# LowLevelv3.net
KiCad netlist of a schematic drawn in EAGLE
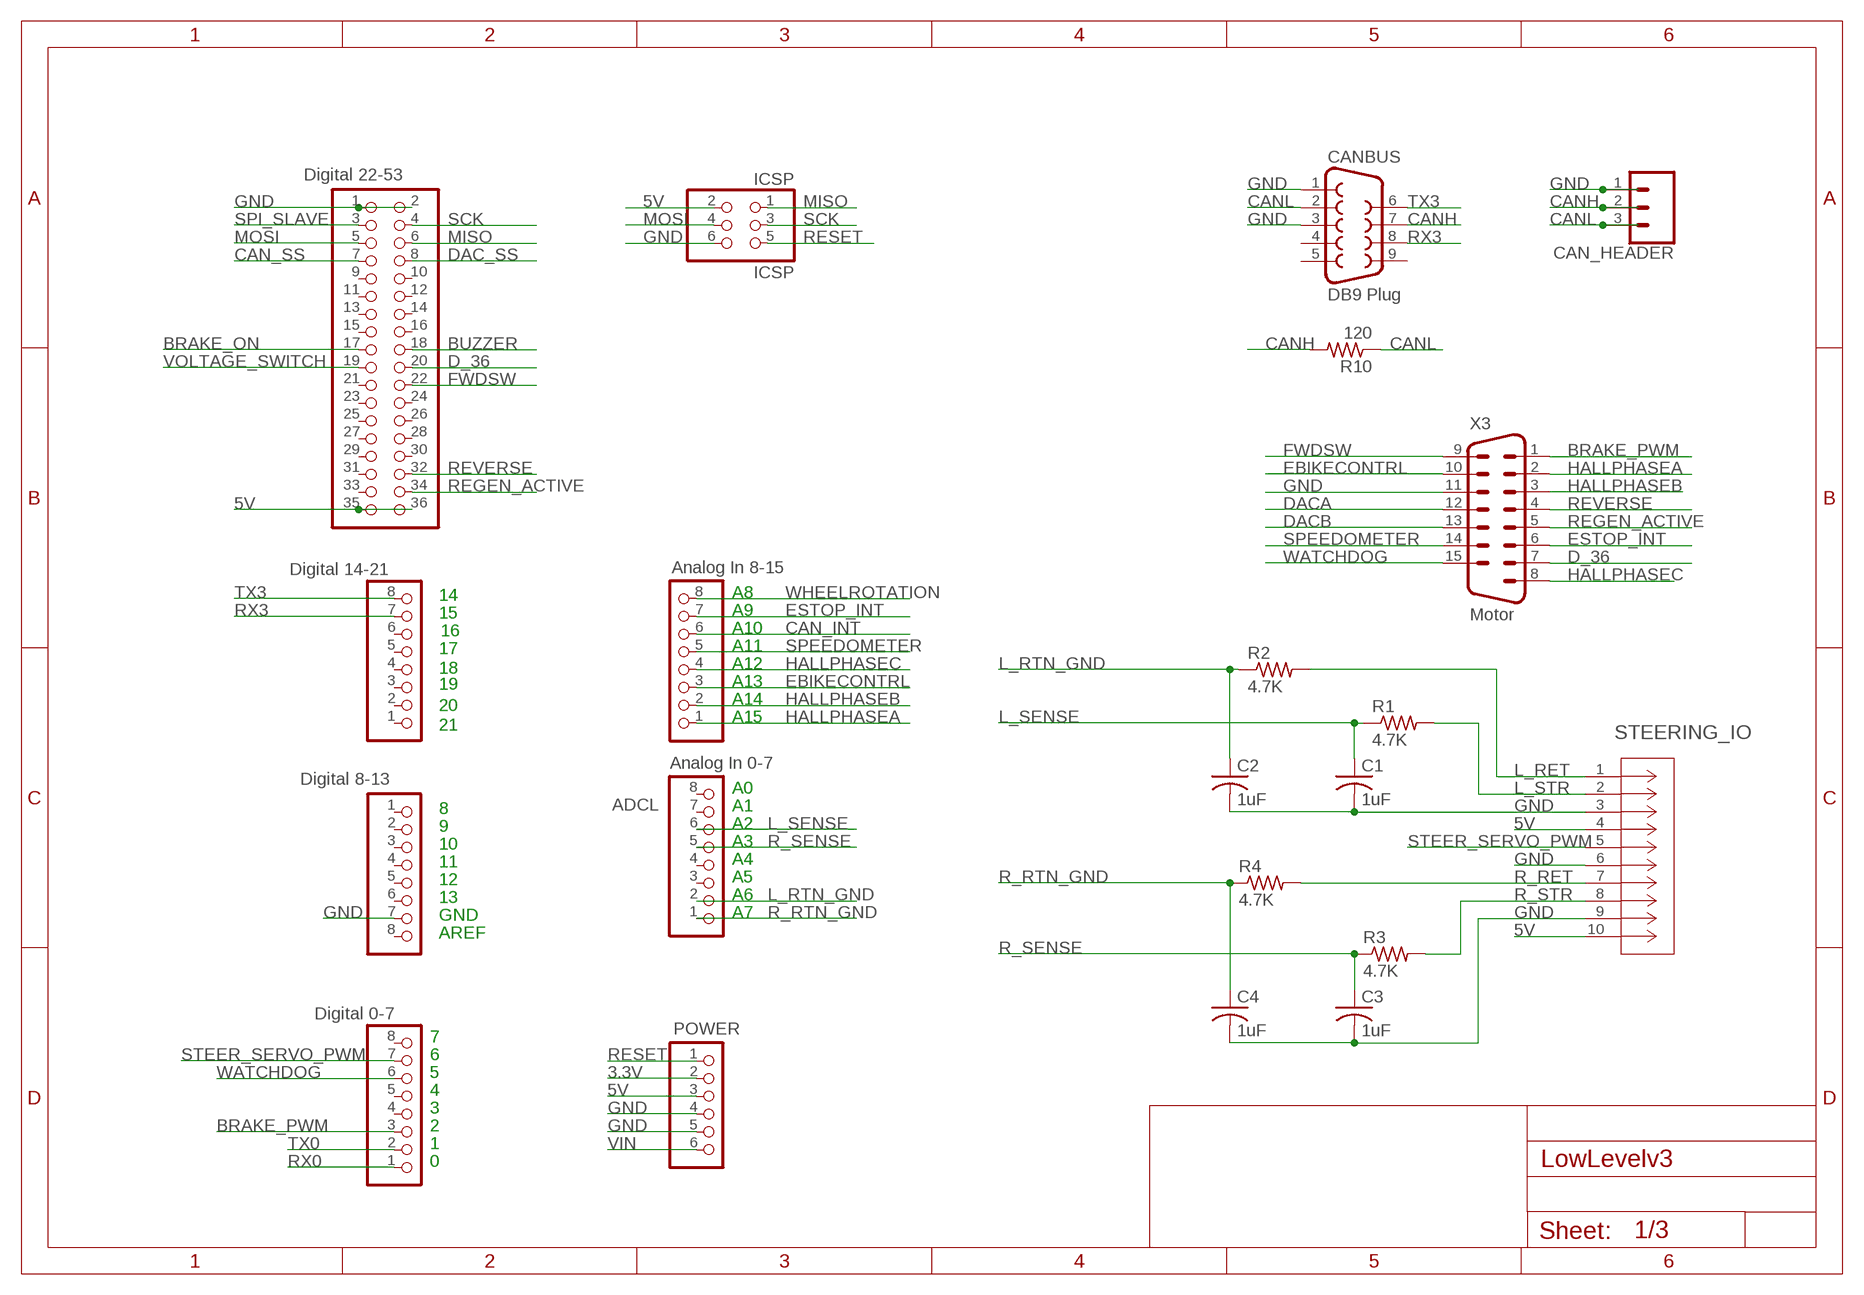
[diagram p0: schematic, sheet 1]
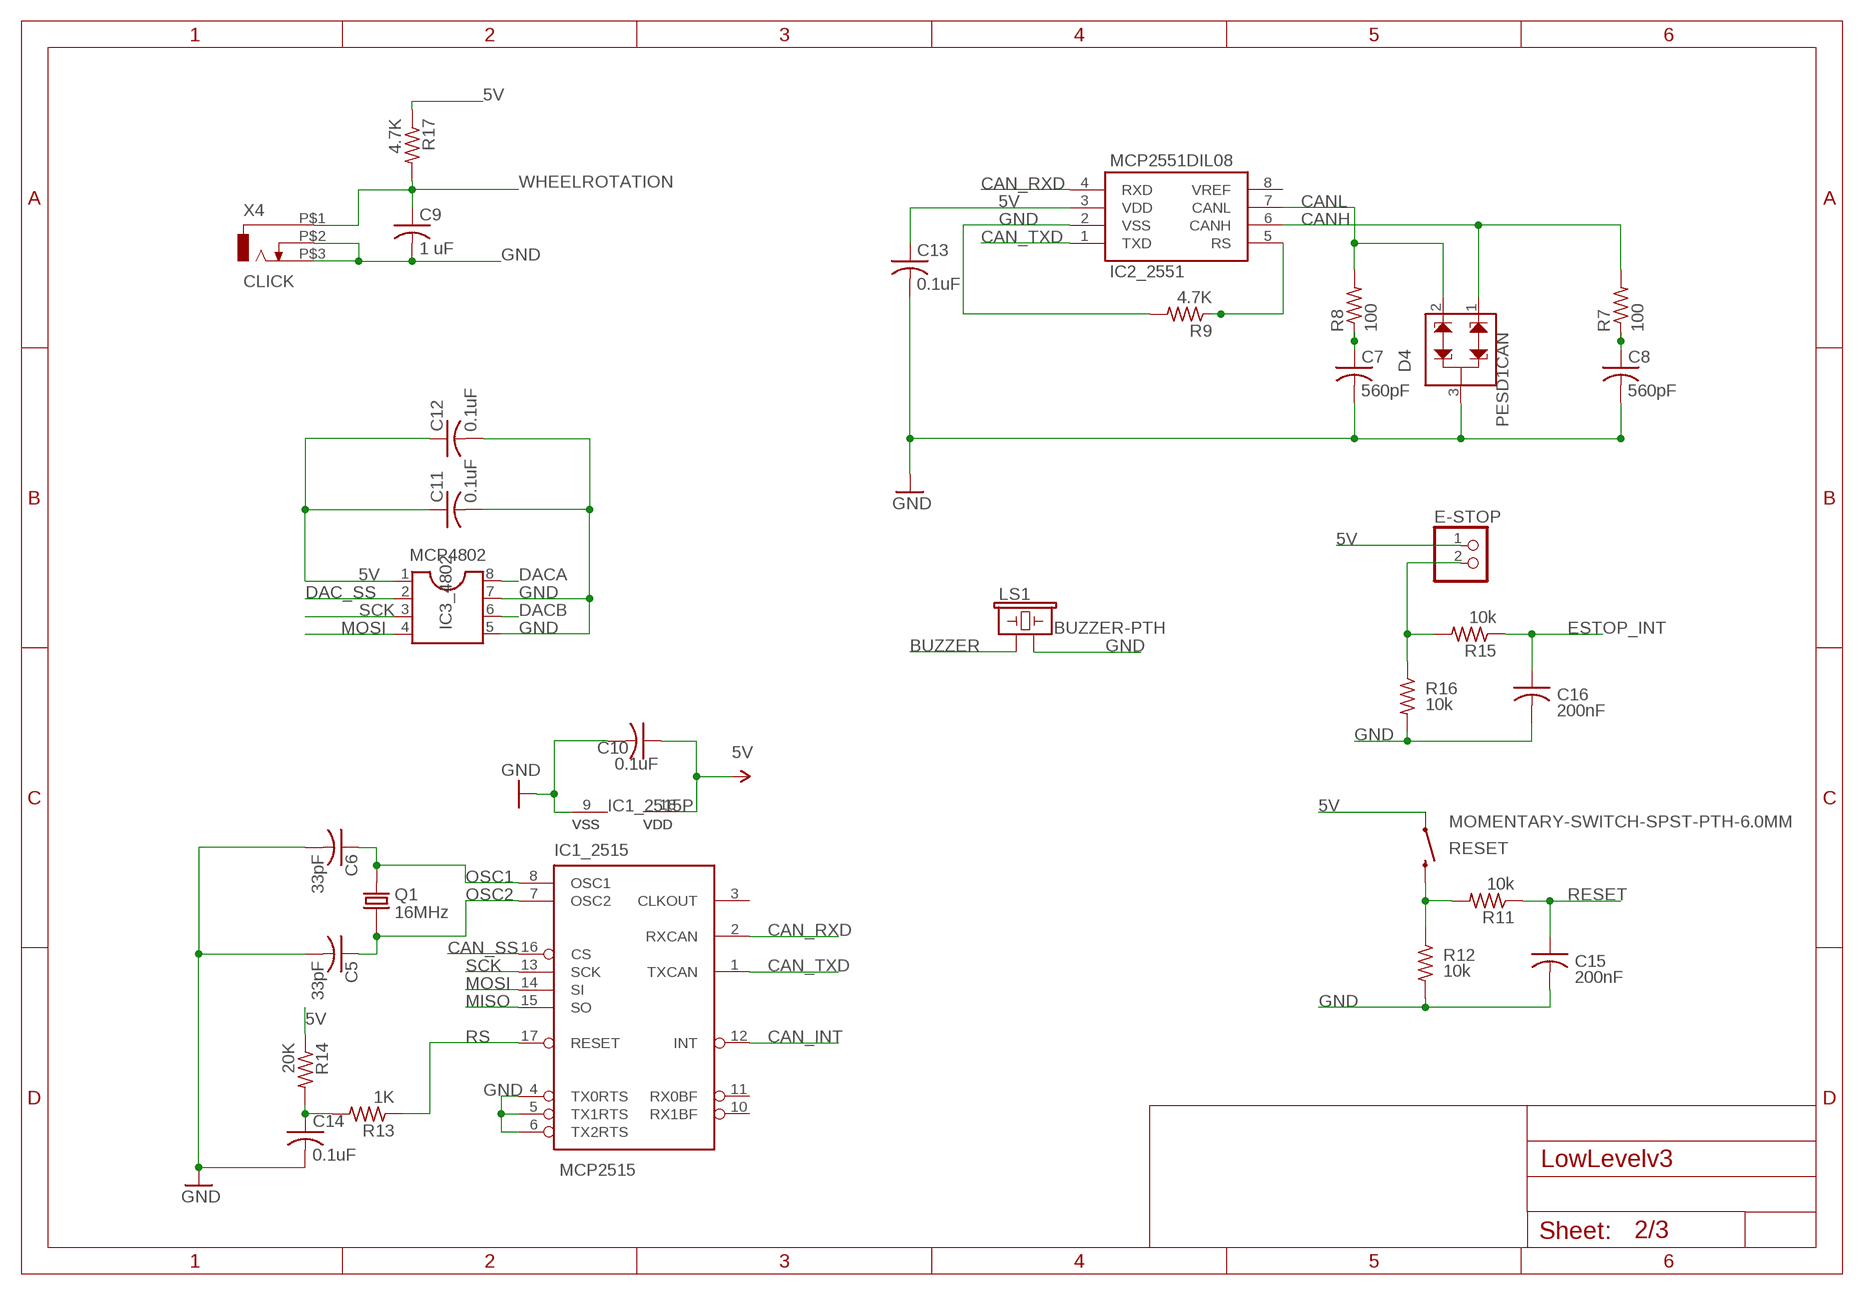
[diagram p1: schematic, sheet 2]
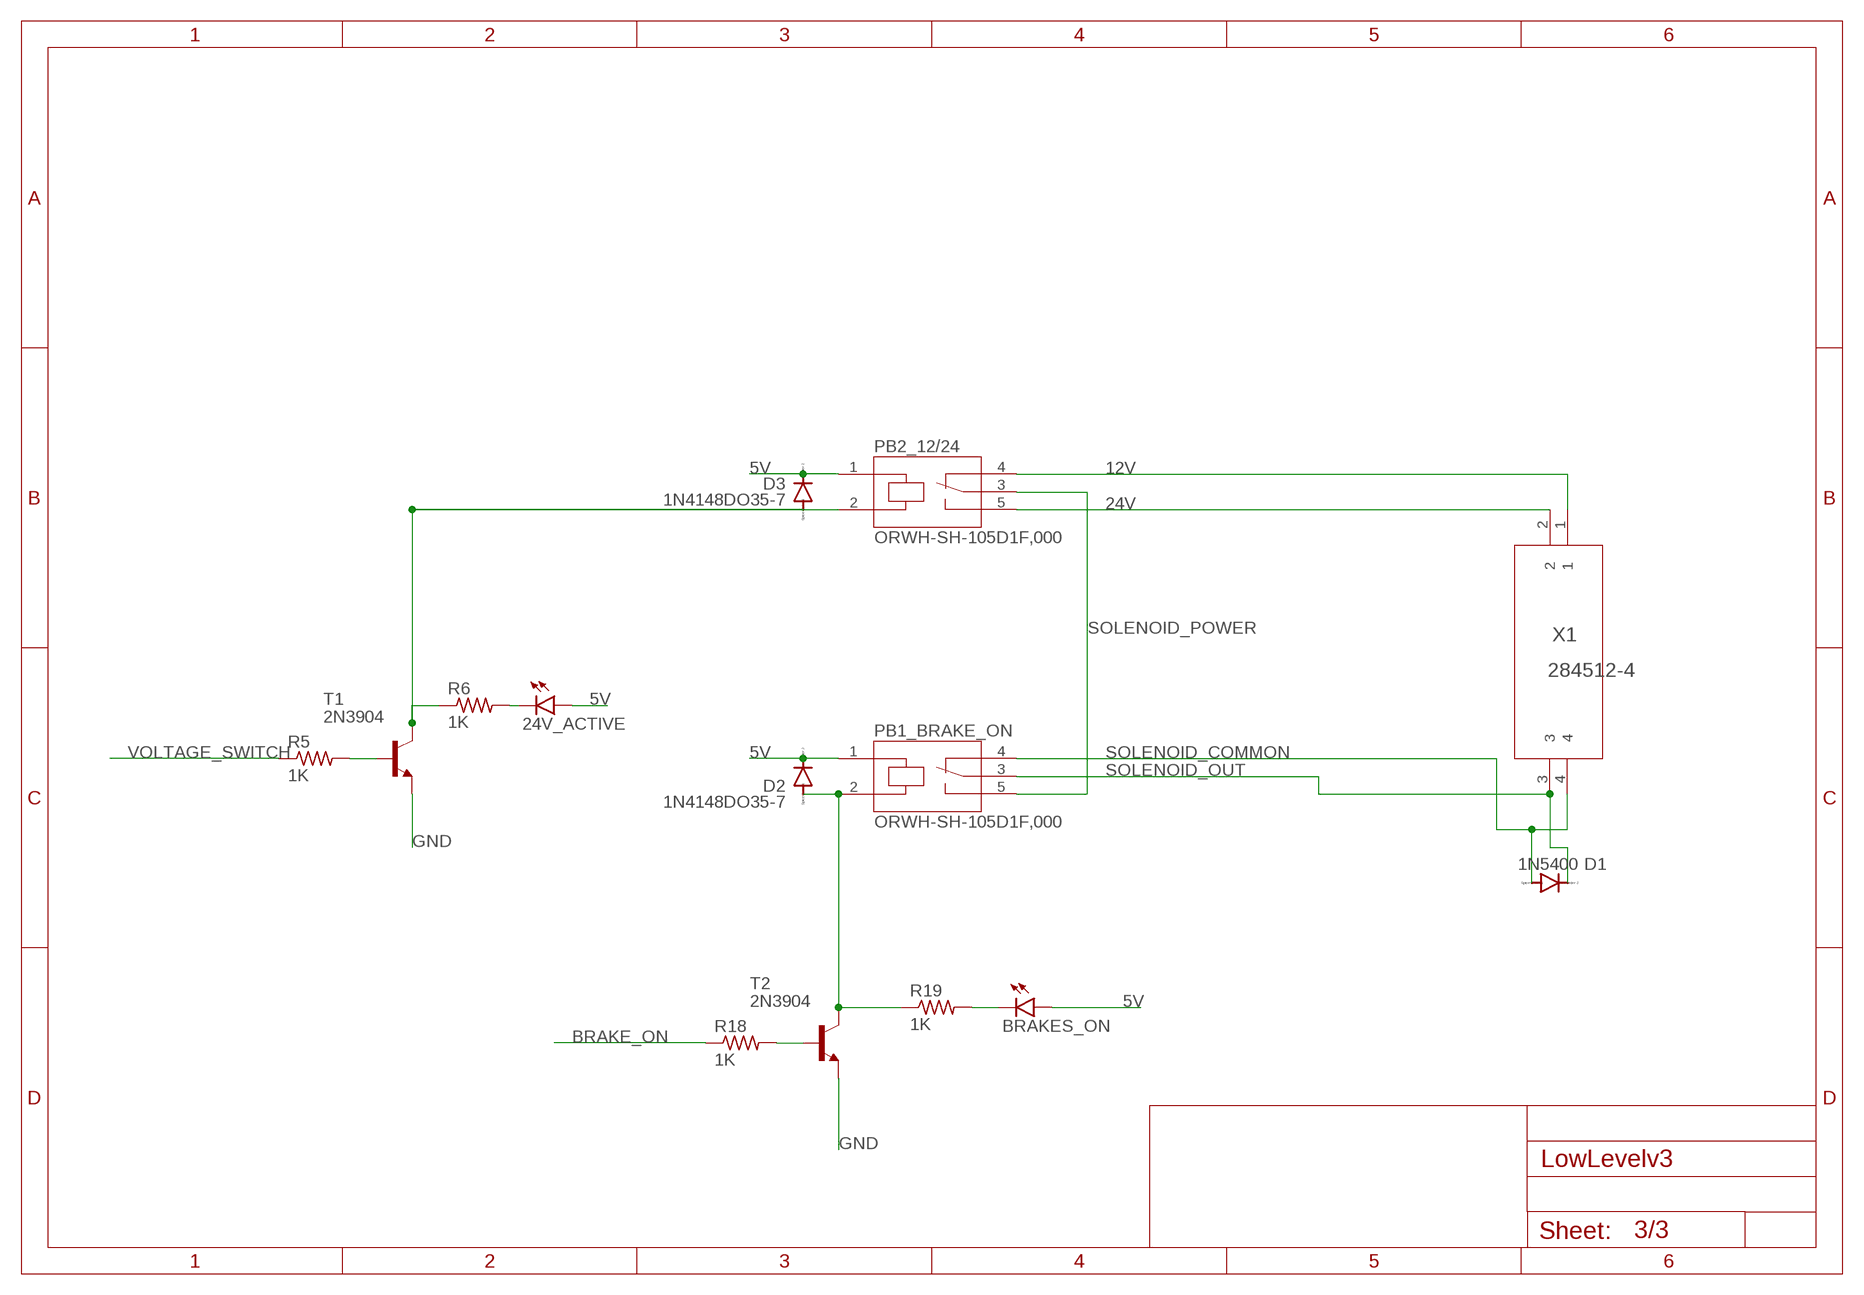
[diagram p2: schematic, sheet 3]

(export (version "E")
  (design (tool "Eeschema 10.0.6"))
  (components
    (comp (ref "C5")
      (value "33pF")
      (footprint "eagle-import:C1206")
      (libsource (lib "eagle-import") (part "C-USC1206"))
    )
    (comp (ref "C6")
      (value "33pF")
      (footprint "eagle-import:C1206")
      (libsource (lib "eagle-import") (part "C-USC1206"))
    )
    (comp (ref "C7")
      (value "560pF")
      (footprint "eagle-import:C1206")
      (libsource (lib "eagle-import") (part "C-USC1206"))
    )
    (comp (ref "C8")
      (value "560pF")
      (footprint "eagle-import:C1206")
      (libsource (lib "eagle-import") (part "C-USC1206"))
    )
    (comp (ref "C9")
      (value "1 uF")
      (footprint "eagle-import:C1206")
      (libsource (lib "eagle-import") (part "C-USC1206"))
    )
    (comp (ref "C10")
      (value "0.1uF")
      (footprint "eagle-import:C1206")
      (libsource (lib "eagle-import") (part "C-USC1206"))
    )
    (comp (ref "C11")
      (value "0.1uF")
      (footprint "eagle-import:C1206")
      (libsource (lib "eagle-import") (part "C-USC1206"))
    )
    (comp (ref "C12")
      (value "0.1uF")
      (footprint "eagle-import:C1206")
      (libsource (lib "eagle-import") (part "C-USC1206"))
    )
    (comp (ref "C13")
      (value "0.1uF")
      (footprint "eagle-import:C1206")
      (libsource (lib "eagle-import") (part "C-USC1206"))
    )
    (comp (ref "C14")
      (value "0.1uF")
      (footprint "eagle-import:C1206")
      (libsource (lib "eagle-import") (part "C-USC1206"))
    )
    (comp (ref "C15")
      (value "200nF")
      (footprint "eagle-import:C1206")
      (libsource (lib "eagle-import") (part "C-USC1206"))
    )
    (comp (ref "C16")
      (value "200nF")
      (footprint "eagle-import:C1206")
      (libsource (lib "eagle-import") (part "C-USC1206"))
    )
    (comp (ref "D4")
      (value "PESD1CAN")
      (footprint "eagle-import:SPARKFUN-DISCRETESEMI_SOT23-3")
      (fields (field (name "SPICEPREFIX") "J"))
      (libsource (lib "eagle-import") (part "PESD1CAN"))
    )
    (comp (ref "E-STOP")
      (value "PINHD-1X2")
      (footprint "eagle-import:1X02")
      (libsource (lib "eagle-import") (part "PINHD-1X2"))
    )
    (comp (ref "IC1_2515")
      (value "MCP2515")
      (footprint "eagle-import:DIP18")
      (fields (field (name "SPICEPREFIX") "X"))
      (libsource (lib "eagle-import") (part "MCP2515(MCP2510)P"))
    )
    (comp (ref "IC2_2551")
      (value "MCP2551DIL08")
      (footprint "eagle-import:IC-PACKAGE_DIL08")
      (fields (field (name "SPICEPREFIX") "X"))
      (libsource (lib "eagle-import") (part "MCP2551DIL08"))
    )
    (comp (ref "IC3_4802")
      (value "MCP4802")
      (footprint "eagle-import:DIL08")
      (libsource (lib "eagle-import") (part "DIL8"))
    )
    (comp (ref "LS1")
      (value "BUZZER-PTH")
      (footprint "eagle-import:BUZZER-12MM")
      (libsource (lib "eagle-import") (part "BUZZER-PTH"))
    )
    (comp (ref "Q1")
      (value "16MHz")
      (footprint "eagle-import:XTAL_ECS-160-20-46X")
      (fields
        (field (name "DIGI-KEY_PART_NUMBER") "XC1759-ND")
        (field (name "MF") "ECS Inc.")
        (field (name "MP") "ECS-160-20-46X")
        (field (name "SPICEPREFIX") "B")
      )
      (libsource (lib "eagle-import") (part "ECS-160-20-46X"))
    )
    (comp (ref "R7")
      (value "100")
      (footprint "eagle-import:R1206")
      (libsource (lib "eagle-import") (part "R-US_R1206"))
    )
    (comp (ref "R8")
      (value "100")
      (footprint "eagle-import:R1206")
      (libsource (lib "eagle-import") (part "R-US_R1206"))
    )
    (comp (ref "R9")
      (value "4.7K")
      (footprint "eagle-import:R1206")
      (libsource (lib "eagle-import") (part "R-US_R1206"))
    )
    (comp (ref "R11")
      (value "10k")
      (footprint "eagle-import:R1206")
      (libsource (lib "eagle-import") (part "R-US_R1206"))
    )
    (comp (ref "R12")
      (value "10k")
      (footprint "eagle-import:R1206")
      (libsource (lib "eagle-import") (part "R-US_R1206"))
    )
    (comp (ref "R13")
      (value "1K")
      (footprint "eagle-import:R1206")
      (libsource (lib "eagle-import") (part "R-US_R1206"))
    )
    (comp (ref "R14")
      (value "20K")
      (footprint "eagle-import:R1206")
      (libsource (lib "eagle-import") (part "R-US_R1206"))
    )
    (comp (ref "R15")
      (value "10k")
      (footprint "eagle-import:R1206")
      (libsource (lib "eagle-import") (part "R-US_R1206"))
    )
    (comp (ref "R16")
      (value "10k")
      (footprint "eagle-import:R1206")
      (libsource (lib "eagle-import") (part "R-US_R1206"))
    )
    (comp (ref "R17")
      (value "4.7K")
      (footprint "eagle-import:R1206")
      (libsource (lib "eagle-import") (part "R-US_R1206"))
    )
    (comp (ref "RESET")
      (value "MOMENTARY-SWITCH-SPST-PTH-6.0MM")
      (footprint "eagle-import:TACTILE_SWITCH_PTH_6.0MM")
      (libsource (lib "eagle-import") (part "MOMENTARY-SWITCH-SPST-PTH-6.0MM"))
    )
    (comp (ref "X4")
      (value "CLICK")
      (footprint "eagle-import:ODO_JACK")
      (libsource (lib "eagle-import") (part "ODO_JACK"))
    )
    (comp (ref "24V_ACTIVE")
      (value "LED3MM")
      (footprint "eagle-import:LED3MM")
      (libsource (lib "eagle-import") (part "LED3MM"))
    )
    (comp (ref "BRAKES_ON")
      (value "LED3MM")
      (footprint "eagle-import:LED3MM")
      (libsource (lib "eagle-import") (part "LED3MM"))
    )
    (comp (ref "D1")
      (value "1N5400")
      (footprint "eagle-import:DO201-15")
      (libsource (lib "eagle-import") (part "1N5400"))
    )
    (comp (ref "D2")
      (value "1N4148DO35-7")
      (footprint "eagle-import:DO35-7")
      (libsource (lib "eagle-import") (part "1N4148DO35-7"))
    )
    (comp (ref "D3")
      (value "1N4148DO35-7")
      (footprint "eagle-import:DO35-7")
      (libsource (lib "eagle-import") (part "1N4148DO35-7"))
    )
    (comp (ref "PB1_BRAKE_ON")
      (value "ORWH-SH-105D1F,000")
      (footprint "eagle-import:TE_ORWH-SH-105D1F,000")
      (fields (field (name "DIGI-KEY_PART_NUMBER") "PB2032-ND") (field (name "MF") "TE"))
      (libsource (lib "eagle-import") (part "ORWH-SH-105D1F,000"))
    )
    (comp (ref "PB2_12/24")
      (value "ORWH-SH-105D1F,000")
      (footprint "eagle-import:TE_ORWH-SH-105D1F,000")
      (fields (field (name "DIGI-KEY_PART_NUMBER") "PB2032-ND") (field (name "MF") "TE"))
      (libsource (lib "eagle-import") (part "ORWH-SH-105D1F,000"))
    )
    (comp (ref "R5")
      (value "1K")
      (footprint "eagle-import:R1206")
      (libsource (lib "eagle-import") (part "R-US_R1206"))
    )
    (comp (ref "R6")
      (value "1K")
      (footprint "eagle-import:R1206")
      (libsource (lib "eagle-import") (part "R-US_R1206"))
    )
    (comp (ref "R18")
      (value "1K")
      (footprint "eagle-import:R1206")
      (libsource (lib "eagle-import") (part "R-US_R1206"))
    )
    (comp (ref "R19")
      (value "1K")
      (footprint "eagle-import:R1206")
      (libsource (lib "eagle-import") (part "R-US_R1206"))
    )
    (comp (ref "T1")
      (value "2N3904")
      (footprint "eagle-import:TO92")
      (libsource (lib "eagle-import") (part "2N3904"))
    )
    (comp (ref "T2")
      (value "2N3904")
      (footprint "eagle-import:TO92")
      (libsource (lib "eagle-import") (part "2N3904"))
    )
    (comp (ref "X1")
      (value "284512-4")
      (footprint "eagle-import:284512-4")
      (fields (field (name "MANUFACTURER_PART_NUMBER") "2845124"))
      (libsource (lib "eagle-import") (part "284512-4"))
    )
    (comp (ref "ADCH")
      (value "Analog In 8-15")
      (footprint "eagle-import:1X08")
      (libsource (lib "eagle-import") (part "PINHD-1X8"))
    )
    (comp (ref "ADCL")
      (value "Analog In 0-7")
      (footprint "eagle-import:1X08")
      (libsource (lib "eagle-import") (part "PINHD-1X8"))
    )
    (comp (ref "C1")
      (value "1uF")
      (footprint "eagle-import:C1206")
      (libsource (lib "eagle-import") (part "C-USC1206"))
    )
    (comp (ref "C2")
      (value "1uF")
      (footprint "eagle-import:C1206")
      (libsource (lib "eagle-import") (part "C-USC1206"))
    )
    (comp (ref "C3")
      (value "1uF")
      (footprint "eagle-import:C1206")
      (libsource (lib "eagle-import") (part "C-USC1206"))
    )
    (comp (ref "C4")
      (value "1uF")
      (footprint "eagle-import:C1206")
      (libsource (lib "eagle-import") (part "C-USC1206"))
    )
    (comp (ref "CANBUS")
      (value "DB9 Plug")
      (footprint "eagle-import:DB9")
      (fields (field (name "SPICEPREFIX") "X"))
      (libsource (lib "eagle-import") (part "DB9FEMALE"))
    )
    (comp (ref "CAN_HEADER")
      (value "CONN_03-SCREW-5MM")
      (footprint "eagle-import:SCREWTERMINAL-5MM-3")
      (libsource (lib "eagle-import") (part "CONN_03-SCREW-5MM"))
    )
    (comp (ref "DIGITAL_0-7")
      (value "Digital 0-7")
      (footprint "eagle-import:1X08")
      (libsource (lib "eagle-import") (part "PINHD-1X8"))
    )
    (comp (ref "DIGITAL_8-13")
      (value "Digital 8-13")
      (footprint "eagle-import:1X08")
      (libsource (lib "eagle-import") (part "PINHD-1X8"))
    )
    (comp (ref "DIGITAL_14-21")
      (value "Digital 14-21")
      (footprint "eagle-import:1X08")
      (libsource (lib "eagle-import") (part "PINHD-1X8"))
    )
    (comp (ref "ICSP")
      (value "ICSP")
      (footprint "eagle-import:2X03")
      (libsource (lib "eagle-import") (part "PINHD-2X3"))
    )
    (comp (ref "MEGA_EXPANSION")
      (value "Digital 22-53")
      (footprint "eagle-import:PINHEAD_2X18")
      (libsource (lib "eagle-import") (part "PINHEAD_PINHD-2X18"))
    )
    (comp (ref "POWER")
      (value "PINHD-1X6")
      (footprint "eagle-import:1X06")
      (libsource (lib "eagle-import") (part "PINHD-1X6"))
    )
    (comp (ref "R1")
      (value "4.7K")
      (footprint "eagle-import:R1206")
      (libsource (lib "eagle-import") (part "R-US_R1206"))
    )
    (comp (ref "R2")
      (value "4.7K")
      (footprint "eagle-import:R1206")
      (libsource (lib "eagle-import") (part "R-US_R1206"))
    )
    (comp (ref "R3")
      (value "4.7K")
      (footprint "eagle-import:R1206")
      (libsource (lib "eagle-import") (part "R-US_R1206"))
    )
    (comp (ref "R4")
      (value "4.7K")
      (footprint "eagle-import:R1206")
      (libsource (lib "eagle-import") (part "R-US_R1206"))
    )
    (comp (ref "R10")
      (value "120")
      (footprint "eagle-import:R1206")
      (libsource (lib "eagle-import") (part "R-US_R1206"))
    )
    (comp (ref "STEERING_IO")
      (value "5-104069-4")
      (footprint "eagle-import:CONN_5-104069-4_TYCO")
      (fields (field (name "MANUFACTURER_PART_NUMBER") "51040694"))
      (libsource (lib "eagle-import") (part "5-104069-4"))
    )
    (comp (ref "X3")
      (value "Motor")
      (footprint "eagle-import:182-015-MALE")
      (libsource (lib "eagle-import") (part "M15-182"))
    )
  )
  (nets
    (net (code "1") (name "3.3V") (class "Default")
      (node (ref "POWER") (pin "2") (pinfunction "2_2") (pintype "passive"))
    )
    (net (code "2") (name "5V") (class "Default")
      (node (ref "24V_ACTIVE") (pin "A") (pinfunction "A_A") (pintype "passive"))
      (node (ref "BRAKES_ON") (pin "A") (pinfunction "A_A") (pintype "passive"))
      (node (ref "C10") (pin "1") (pinfunction "1_1") (pintype "passive"))
      (node (ref "C11") (pin "1") (pinfunction "1_1") (pintype "passive"))
      (node (ref "C12") (pin "1") (pinfunction "1_1") (pintype "passive"))
      (node (ref "C13") (pin "1") (pinfunction "1_1") (pintype "passive"))
      (node (ref "D2") (pin "C") (pinfunction "C_C") (pintype "passive"))
      (node (ref "D3") (pin "C") (pinfunction "C_C") (pintype "passive"))
      (node (ref "E-STOP") (pin "1") (pinfunction "1_1") (pintype "passive"))
      (node (ref "IC1_2515") (pin "18") (pinfunction "VDD_18") (pintype "power_in"))
      (node (ref "IC2_2551") (pin "3") (pinfunction "VDD_3") (pintype "bidirectional"))
      (node (ref "IC3_4802") (pin "1") (pinfunction "1_1") (pintype "passive"))
      (node (ref "ICSP") (pin "2") (pinfunction "2_2") (pintype "passive"))
      (node (ref "MEGA_EXPANSION") (pin "35") (pinfunction "35_35") (pintype "passive"))
      (node (ref "MEGA_EXPANSION") (pin "36") (pinfunction "36_36") (pintype "passive"))
      (node (ref "PB1_BRAKE_ON") (pin "1") (pinfunction "C1_1") (pintype "passive"))
      (node (ref "PB2_12/24") (pin "1") (pinfunction "C1_1") (pintype "passive"))
      (node (ref "POWER") (pin "3") (pinfunction "3_3") (pintype "passive"))
      (node (ref "R14") (pin "1") (pinfunction "1_1") (pintype "passive"))
      (node (ref "R17") (pin "1") (pinfunction "1_1") (pintype "passive"))
      (node (ref "RESET") (pin "1") (pinfunction "1_1") (pintype "passive"))
      (node (ref "STEERING_IO") (pin "10") (pinfunction "10_10") (pintype "passive"))
      (node (ref "STEERING_IO") (pin "4") (pinfunction "4_4") (pintype "passive"))
    )
    (net (code "3") (name "12V") (class "Default")
      (node (ref "PB2_12/24") (pin "4") (pinfunction "NC_4") (pintype "passive"))
      (node (ref "X1") (pin "1") (pinfunction "1_1") (pintype "passive"))
    )
    (net (code "4") (name "24V") (class "Default")
      (node (ref "PB2_12/24") (pin "5") (pinfunction "NO_5") (pintype "passive"))
      (node (ref "X1") (pin "2") (pinfunction "2_2") (pintype "passive"))
    )
    (net (code "5") (name "BRAKE_ON") (class "Default")
      (node (ref "MEGA_EXPANSION") (pin "17") (pinfunction "17_17") (pintype "passive"))
      (node (ref "R18") (pin "1") (pinfunction "1_1") (pintype "passive"))
    )
    (net (code "6") (name "BRAKE_PWM") (class "Default")
      (node (ref "DIGITAL_0-7") (pin "3") (pinfunction "3_3") (pintype "passive"))
      (node (ref "X3") (pin "1") (pinfunction "1_1") (pintype "passive"))
    )
    (net (code "7") (name "BUZZER") (class "Default")
      (node (ref "LS1") (pin "+") (pinfunction "1_+") (pintype "passive"))
      (node (ref "MEGA_EXPANSION") (pin "18") (pinfunction "18_18") (pintype "passive"))
    )
    (net (code "8") (name "CANH") (class "Default")
      (node (ref "CANBUS") (pin "7") (pinfunction "7_7") (pintype "passive"))
      (node (ref "CAN_HEADER") (pin "2") (pinfunction "2_2") (pintype "passive"))
      (node (ref "D4") (pin "1") (pinfunction "1_1") (pintype "bidirectional"))
      (node (ref "IC2_2551") (pin "6") (pinfunction "CANH_6") (pintype "bidirectional"))
      (node (ref "R10") (pin "2") (pinfunction "2_2") (pintype "passive"))
      (node (ref "R7") (pin "2") (pinfunction "2_2") (pintype "passive"))
    )
    (net (code "9") (name "CANL") (class "Default")
      (node (ref "CANBUS") (pin "2") (pinfunction "2_2") (pintype "passive"))
      (node (ref "CAN_HEADER") (pin "3") (pinfunction "3_3") (pintype "passive"))
      (node (ref "D4") (pin "2") (pinfunction "2_2") (pintype "bidirectional"))
      (node (ref "IC2_2551") (pin "7") (pinfunction "CANL_7") (pintype "bidirectional"))
      (node (ref "R10") (pin "1") (pinfunction "1_1") (pintype "passive"))
      (node (ref "R8") (pin "2") (pinfunction "2_2") (pintype "passive"))
    )
    (net (code "10") (name "CAN_INT") (class "Default")
      (node (ref "ADCH") (pin "6") (pinfunction "6_6") (pintype "passive"))
      (node (ref "IC1_2515") (pin "12") (pinfunction "INT_12") (pintype "output"))
    )
    (net (code "11") (name "CAN_RXD") (class "Default")
      (node (ref "IC1_2515") (pin "2") (pinfunction "RXCAN_2") (pintype "input"))
      (node (ref "IC2_2551") (pin "4") (pinfunction "RXD_4") (pintype "bidirectional"))
    )
    (net (code "12") (name "CAN_SS") (class "Default")
      (node (ref "IC1_2515") (pin "16") (pinfunction "CS_16") (pintype "input"))
      (node (ref "MEGA_EXPANSION") (pin "7") (pinfunction "7_7") (pintype "passive"))
    )
    (net (code "13") (name "CAN_TXD") (class "Default")
      (node (ref "IC1_2515") (pin "1") (pinfunction "TXCAN_1") (pintype "output"))
      (node (ref "IC2_2551") (pin "1") (pinfunction "TXD_1") (pintype "bidirectional"))
    )
    (net (code "14") (name "DACA") (class "Default")
      (node (ref "IC3_4802") (pin "8") (pinfunction "8_8") (pintype "passive"))
      (node (ref "X3") (pin "12") (pinfunction "12_12") (pintype "passive"))
    )
    (net (code "15") (name "DACB") (class "Default")
      (node (ref "IC3_4802") (pin "6") (pinfunction "6_6") (pintype "passive"))
      (node (ref "X3") (pin "13") (pinfunction "13_13") (pintype "passive"))
    )
    (net (code "16") (name "DAC_SS") (class "Default")
      (node (ref "IC3_4802") (pin "2") (pinfunction "2_2") (pintype "passive"))
      (node (ref "MEGA_EXPANSION") (pin "8") (pinfunction "8_8") (pintype "passive"))
    )
    (net (code "17") (name "D_36") (class "Default")
      (node (ref "MEGA_EXPANSION") (pin "20") (pinfunction "20_20") (pintype "passive"))
      (node (ref "X3") (pin "7") (pinfunction "7_7") (pintype "passive"))
    )
    (net (code "18") (name "EBIKECONTRL") (class "Default")
      (node (ref "ADCH") (pin "3") (pinfunction "3_3") (pintype "passive"))
      (node (ref "X3") (pin "10") (pinfunction "10_10") (pintype "passive"))
    )
    (net (code "19") (name "ESTOP_INT") (class "Default")
      (node (ref "ADCH") (pin "7") (pinfunction "7_7") (pintype "passive"))
      (node (ref "C16") (pin "1") (pinfunction "1_1") (pintype "passive"))
      (node (ref "R15") (pin "1") (pinfunction "1_1") (pintype "passive"))
      (node (ref "X3") (pin "6") (pinfunction "6_6") (pintype "passive"))
    )
    (net (code "20") (name "FWDSW") (class "Default")
      (node (ref "MEGA_EXPANSION") (pin "22") (pinfunction "22_22") (pintype "passive"))
      (node (ref "X3") (pin "9") (pinfunction "9_9") (pintype "passive"))
    )
    (net (code "21") (name "GND") (class "Default")
      (node (ref "C1") (pin "2") (pinfunction "2_2") (pintype "passive"))
      (node (ref "C10") (pin "2") (pinfunction "2_2") (pintype "passive"))
      (node (ref "C11") (pin "2") (pinfunction "2_2") (pintype "passive"))
      (node (ref "C12") (pin "2") (pinfunction "2_2") (pintype "passive"))
      (node (ref "C13") (pin "2") (pinfunction "2_2") (pintype "passive"))
      (node (ref "C14") (pin "2") (pinfunction "2_2") (pintype "passive"))
      (node (ref "C15") (pin "2") (pinfunction "2_2") (pintype "passive"))
      (node (ref "C16") (pin "2") (pinfunction "2_2") (pintype "passive"))
      (node (ref "C2") (pin "2") (pinfunction "2_2") (pintype "passive"))
      (node (ref "C3") (pin "2") (pinfunction "2_2") (pintype "passive"))
      (node (ref "C4") (pin "2") (pinfunction "2_2") (pintype "passive"))
      (node (ref "C5") (pin "2") (pinfunction "2_2") (pintype "passive"))
      (node (ref "C6") (pin "2") (pinfunction "2_2") (pintype "passive"))
      (node (ref "C7") (pin "2") (pinfunction "2_2") (pintype "passive"))
      (node (ref "C8") (pin "2") (pinfunction "2_2") (pintype "passive"))
      (node (ref "C9") (pin "2") (pinfunction "2_2") (pintype "passive"))
      (node (ref "CANBUS") (pin "1") (pinfunction "1_1") (pintype "passive"))
      (node (ref "CANBUS") (pin "3") (pinfunction "3_3") (pintype "passive"))
      (node (ref "CAN_HEADER") (pin "1") (pinfunction "1_1") (pintype "passive"))
      (node (ref "D4") (pin "3") (pinfunction "3_3") (pintype "bidirectional"))
      (node (ref "DIGITAL_8-13") (pin "7") (pinfunction "7_7") (pintype "passive"))
      (node (ref "IC1_2515") (pin "4") (pinfunction "TX0RTS_4") (pintype "input"))
      (node (ref "IC1_2515") (pin "5") (pinfunction "TX1RTS_5") (pintype "input"))
      (node (ref "IC1_2515") (pin "6") (pinfunction "TX2RTS_6") (pintype "input"))
      (node (ref "IC1_2515") (pin "9") (pinfunction "VSS_9") (pintype "power_in"))
      (node (ref "IC2_2551") (pin "2") (pinfunction "VSS_2") (pintype "bidirectional"))
      (node (ref "IC3_4802") (pin "5") (pinfunction "5_5") (pintype "passive"))
      (node (ref "IC3_4802") (pin "7") (pinfunction "7_7") (pintype "passive"))
      (node (ref "ICSP") (pin "6") (pinfunction "6_6") (pintype "passive"))
      (node (ref "LS1") (pin "-") (pinfunction "2_-") (pintype "passive"))
      (node (ref "MEGA_EXPANSION") (pin "1") (pinfunction "1_1") (pintype "passive"))
      (node (ref "MEGA_EXPANSION") (pin "2") (pinfunction "2_2") (pintype "passive"))
      (node (ref "POWER") (pin "4") (pinfunction "4_4") (pintype "passive"))
      (node (ref "POWER") (pin "5") (pinfunction "5_5") (pintype "passive"))
      (node (ref "R12") (pin "2") (pinfunction "2_2") (pintype "passive"))
      (node (ref "R16") (pin "2") (pinfunction "2_2") (pintype "passive"))
      (node (ref "R9") (pin "2") (pinfunction "2_2") (pintype "passive"))
      (node (ref "STEERING_IO") (pin "3") (pinfunction "3_3") (pintype "passive"))
      (node (ref "STEERING_IO") (pin "6") (pinfunction "6_6") (pintype "passive"))
      (node (ref "STEERING_IO") (pin "9") (pinfunction "9_9") (pintype "passive"))
      (node (ref "T1") (pin "3") (pinfunction "E_3") (pintype "passive"))
      (node (ref "T2") (pin "3") (pinfunction "E_3") (pintype "passive"))
      (node (ref "X3") (pin "11") (pinfunction "11_11") (pintype "passive"))
      (node (ref "X4") (pin "P$2") (pinfunction "2_P$2") (pintype "passive"))
      (node (ref "X4") (pin "P$3") (pinfunction "3_P$3") (pintype "passive"))
    )
    (net (code "22") (name "HALLPHASEA") (class "Default")
      (node (ref "ADCH") (pin "1") (pinfunction "1_1") (pintype "passive"))
      (node (ref "X3") (pin "2") (pinfunction "2_2") (pintype "passive"))
    )
    (net (code "23") (name "HALLPHASEB") (class "Default")
      (node (ref "ADCH") (pin "2") (pinfunction "2_2") (pintype "passive"))
      (node (ref "X3") (pin "3") (pinfunction "3_3") (pintype "passive"))
    )
    (net (code "24") (name "HALLPHASEC") (class "Default")
      (node (ref "ADCH") (pin "4") (pinfunction "4_4") (pintype "passive"))
      (node (ref "X3") (pin "8") (pinfunction "8_8") (pintype "passive"))
    )
    (net (code "25") (name "L_RET") (class "Default")
      (node (ref "R2") (pin "2") (pinfunction "2_2") (pintype "passive"))
      (node (ref "STEERING_IO") (pin "1") (pinfunction "1_1") (pintype "passive"))
    )
    (net (code "26") (name "L_RTN_GND") (class "Default")
      (node (ref "ADCL") (pin "2") (pinfunction "2_2") (pintype "passive"))
      (node (ref "C2") (pin "1") (pinfunction "1_1") (pintype "passive"))
      (node (ref "R2") (pin "1") (pinfunction "1_1") (pintype "passive"))
    )
    (net (code "27") (name "L_SENSE") (class "Default")
      (node (ref "ADCL") (pin "6") (pinfunction "6_6") (pintype "passive"))
      (node (ref "C1") (pin "1") (pinfunction "1_1") (pintype "passive"))
      (node (ref "R1") (pin "1") (pinfunction "1_1") (pintype "passive"))
    )
    (net (code "28") (name "L_STR") (class "Default")
      (node (ref "R1") (pin "2") (pinfunction "2_2") (pintype "passive"))
      (node (ref "STEERING_IO") (pin "2") (pinfunction "2_2") (pintype "passive"))
    )
    (net (code "29") (name "MISO") (class "Default")
      (node (ref "IC1_2515") (pin "15") (pinfunction "SO_15") (pintype "output"))
      (node (ref "ICSP") (pin "1") (pinfunction "1_1") (pintype "passive"))
      (node (ref "MEGA_EXPANSION") (pin "6") (pinfunction "6_6") (pintype "passive"))
    )
    (net (code "30") (name "MOSI") (class "Default")
      (node (ref "IC1_2515") (pin "14") (pinfunction "SI_14") (pintype "input"))
      (node (ref "IC3_4802") (pin "4") (pinfunction "4_4") (pintype "passive"))
      (node (ref "ICSP") (pin "4") (pinfunction "4_4") (pintype "passive"))
      (node (ref "MEGA_EXPANSION") (pin "5") (pinfunction "5_5") (pintype "passive"))
    )
    (net (code "31") (name "Net-(24V_ACTIVE-C)") (class "Default")
      (node (ref "24V_ACTIVE") (pin "K") (pinfunction "C_K") (pintype "passive"))
      (node (ref "R6") (pin "2") (pinfunction "2_2") (pintype "passive"))
    )
    (net (code "32") (name "Net-(BRAKES_ON-C)") (class "Default")
      (node (ref "BRAKES_ON") (pin "K") (pinfunction "C_K") (pintype "passive"))
      (node (ref "R19") (pin "2") (pinfunction "2_2") (pintype "passive"))
    )
    (net (code "33") (name "Net-(C7-Pad1)") (class "Default")
      (node (ref "C7") (pin "1") (pinfunction "1_1") (pintype "passive"))
      (node (ref "R8") (pin "1") (pinfunction "1_1") (pintype "passive"))
    )
    (net (code "34") (name "Net-(C8-Pad1)") (class "Default")
      (node (ref "C8") (pin "1") (pinfunction "1_1") (pintype "passive"))
      (node (ref "R7") (pin "1") (pinfunction "1_1") (pintype "passive"))
    )
    (net (code "35") (name "Net-(C14-Pad1)") (class "Default")
      (node (ref "C14") (pin "1") (pinfunction "1_1") (pintype "passive"))
      (node (ref "R13") (pin "2") (pinfunction "2_2") (pintype "passive"))
      (node (ref "R14") (pin "2") (pinfunction "2_2") (pintype "passive"))
    )
    (net (code "36") (name "Net-(E-STOP-Pad2)") (class "Default")
      (node (ref "E-STOP") (pin "2") (pinfunction "2_2") (pintype "passive"))
      (node (ref "R15") (pin "2") (pinfunction "2_2") (pintype "passive"))
      (node (ref "R16") (pin "1") (pinfunction "1_1") (pintype "passive"))
    )
    (net (code "37") (name "Net-(IC2_2551-RS)") (class "Default")
      (node (ref "IC2_2551") (pin "5") (pinfunction "RS_5") (pintype "bidirectional"))
      (node (ref "R9") (pin "1") (pinfunction "1_1") (pintype "passive"))
    )
    (net (code "38") (name "Net-(PB1_BRAKE_ON-C2)") (class "Default")
      (node (ref "D2") (pin "A") (pinfunction "A_A") (pintype "passive"))
      (node (ref "PB1_BRAKE_ON") (pin "2") (pinfunction "C2_2") (pintype "passive"))
      (node (ref "R19") (pin "1") (pinfunction "1_1") (pintype "passive"))
      (node (ref "T2") (pin "1") (pinfunction "C_1") (pintype "passive"))
    )
    (net (code "39") (name "Net-(PB2_12/24-C2)") (class "Default")
      (node (ref "D3") (pin "A") (pinfunction "A_A") (pintype "passive"))
      (node (ref "PB2_12/24") (pin "2") (pinfunction "C2_2") (pintype "passive"))
      (node (ref "R6") (pin "1") (pinfunction "1_1") (pintype "passive"))
      (node (ref "T1") (pin "1") (pinfunction "C_1") (pintype "passive"))
    )
    (net (code "40") (name "Net-(RESET-2)") (class "Default")
      (node (ref "R11") (pin "2") (pinfunction "2_2") (pintype "passive"))
      (node (ref "R12") (pin "1") (pinfunction "1_1") (pintype "passive"))
      (node (ref "RESET") (pin "3") (pinfunction "2_3") (pintype "passive"))
    )
    (net (code "41") (name "Net-(T1-B)") (class "Default")
      (node (ref "R5") (pin "2") (pinfunction "2_2") (pintype "passive"))
      (node (ref "T1") (pin "2") (pinfunction "B_2") (pintype "passive"))
    )
    (net (code "42") (name "Net-(T2-B)") (class "Default")
      (node (ref "R18") (pin "2") (pinfunction "2_2") (pintype "passive"))
      (node (ref "T2") (pin "2") (pinfunction "B_2") (pintype "passive"))
    )
    (net (code "43") (name "OSC1") (class "Default")
      (node (ref "C6") (pin "1") (pinfunction "1_1") (pintype "passive"))
      (node (ref "IC1_2515") (pin "8") (pinfunction "OSC1_8") (pintype "input"))
      (node (ref "Q1") (pin "2") (pinfunction "2_2") (pintype "passive"))
    )
    (net (code "44") (name "OSC2") (class "Default")
      (node (ref "C5") (pin "1") (pinfunction "1_1") (pintype "passive"))
      (node (ref "IC1_2515") (pin "7") (pinfunction "OSC2_7") (pintype "output"))
      (node (ref "Q1") (pin "1") (pinfunction "1_1") (pintype "passive"))
    )
    (net (code "45") (name "REGEN_ACTIVE") (class "Default")
      (node (ref "MEGA_EXPANSION") (pin "34") (pinfunction "34_34") (pintype "passive"))
      (node (ref "X3") (pin "5") (pinfunction "5_5") (pintype "passive"))
    )
    (net (code "46") (name "RESET") (class "Default")
      (node (ref "C15") (pin "1") (pinfunction "1_1") (pintype "passive"))
      (node (ref "ICSP") (pin "5") (pinfunction "5_5") (pintype "passive"))
      (node (ref "POWER") (pin "1") (pinfunction "1_1") (pintype "passive"))
      (node (ref "R11") (pin "1") (pinfunction "1_1") (pintype "passive"))
    )
    (net (code "47") (name "REVERSE") (class "Default")
      (node (ref "MEGA_EXPANSION") (pin "32") (pinfunction "32_32") (pintype "passive"))
      (node (ref "X3") (pin "4") (pinfunction "4_4") (pintype "passive"))
    )
    (net (code "48") (name "RS") (class "Default")
      (node (ref "IC1_2515") (pin "17") (pinfunction "RESET_17") (pintype "input"))
      (node (ref "R13") (pin "1") (pinfunction "1_1") (pintype "passive"))
    )
    (net (code "49") (name "RX0") (class "Default")
      (node (ref "DIGITAL_0-7") (pin "1") (pinfunction "1_1") (pintype "passive"))
    )
    (net (code "50") (name "RX3") (class "Default")
      (node (ref "CANBUS") (pin "8") (pinfunction "8_8") (pintype "passive"))
      (node (ref "DIGITAL_14-21") (pin "7") (pinfunction "7_7") (pintype "passive"))
    )
    (net (code "51") (name "R_RET") (class "Default")
      (node (ref "R4") (pin "2") (pinfunction "2_2") (pintype "passive"))
      (node (ref "STEERING_IO") (pin "7") (pinfunction "7_7") (pintype "passive"))
    )
    (net (code "52") (name "R_RTN_GND") (class "Default")
      (node (ref "ADCL") (pin "1") (pinfunction "1_1") (pintype "passive"))
      (node (ref "C4") (pin "1") (pinfunction "1_1") (pintype "passive"))
      (node (ref "R4") (pin "1") (pinfunction "1_1") (pintype "passive"))
    )
    (net (code "53") (name "R_SENSE") (class "Default")
      (node (ref "ADCL") (pin "5") (pinfunction "5_5") (pintype "passive"))
      (node (ref "C3") (pin "1") (pinfunction "1_1") (pintype "passive"))
      (node (ref "R3") (pin "1") (pinfunction "1_1") (pintype "passive"))
    )
    (net (code "54") (name "R_STR") (class "Default")
      (node (ref "R3") (pin "2") (pinfunction "2_2") (pintype "passive"))
      (node (ref "STEERING_IO") (pin "8") (pinfunction "8_8") (pintype "passive"))
    )
    (net (code "55") (name "SCK") (class "Default")
      (node (ref "IC1_2515") (pin "13") (pinfunction "SCK_13") (pintype "input"))
      (node (ref "IC3_4802") (pin "3") (pinfunction "3_3") (pintype "passive"))
      (node (ref "ICSP") (pin "3") (pinfunction "3_3") (pintype "passive"))
      (node (ref "MEGA_EXPANSION") (pin "4") (pinfunction "4_4") (pintype "passive"))
    )
    (net (code "56") (name "SOLENOID_COMMON") (class "Default")
      (node (ref "D1") (pin "A") (pinfunction "A_A") (pintype "passive"))
      (node (ref "PB1_BRAKE_ON") (pin "4") (pinfunction "NC_4") (pintype "passive"))
      (node (ref "X1") (pin "4") (pinfunction "4_4") (pintype "passive"))
    )
    (net (code "57") (name "SOLENOID_OUT") (class "Default")
      (node (ref "D1") (pin "C") (pinfunction "C_C") (pintype "passive"))
      (node (ref "PB1_BRAKE_ON") (pin "3") (pinfunction "C_3") (pintype "passive"))
      (node (ref "X1") (pin "3") (pinfunction "3_3") (pintype "passive"))
    )
    (net (code "58") (name "SOLENOID_POWER") (class "Default")
      (node (ref "PB1_BRAKE_ON") (pin "5") (pinfunction "NO_5") (pintype "passive"))
      (node (ref "PB2_12/24") (pin "3") (pinfunction "C_3") (pintype "passive"))
    )
    (net (code "59") (name "SPEEDOMETER") (class "Default")
      (node (ref "ADCH") (pin "5") (pinfunction "5_5") (pintype "passive"))
      (node (ref "X3") (pin "14") (pinfunction "14_14") (pintype "passive"))
    )
    (net (code "60") (name "SPI_SLAVE") (class "Default")
      (node (ref "MEGA_EXPANSION") (pin "3") (pinfunction "3_3") (pintype "passive"))
    )
    (net (code "61") (name "STEER_SERVO_PWM") (class "Default")
      (node (ref "DIGITAL_0-7") (pin "7") (pinfunction "7_7") (pintype "passive"))
      (node (ref "STEERING_IO") (pin "5") (pinfunction "5_5") (pintype "passive"))
    )
    (net (code "62") (name "TX0") (class "Default")
      (node (ref "DIGITAL_0-7") (pin "2") (pinfunction "2_2") (pintype "passive"))
    )
    (net (code "63") (name "TX3") (class "Default")
      (node (ref "CANBUS") (pin "6") (pinfunction "6_6") (pintype "passive"))
      (node (ref "DIGITAL_14-21") (pin "8") (pinfunction "8_8") (pintype "passive"))
    )
    (net (code "64") (name "VIN") (class "Default")
      (node (ref "POWER") (pin "6") (pinfunction "6_6") (pintype "passive"))
    )
    (net (code "65") (name "VOLTAGE_SWITCH") (class "Default")
      (node (ref "MEGA_EXPANSION") (pin "19") (pinfunction "19_19") (pintype "passive"))
      (node (ref "R5") (pin "1") (pinfunction "1_1") (pintype "passive"))
    )
    (net (code "66") (name "WATCHDOG") (class "Default")
      (node (ref "DIGITAL_0-7") (pin "6") (pinfunction "6_6") (pintype "passive"))
      (node (ref "X3") (pin "15") (pinfunction "15_15") (pintype "passive"))
    )
    (net (code "67") (name "WHEELROTATION") (class "Default")
      (node (ref "ADCH") (pin "8") (pinfunction "8_8") (pintype "passive"))
      (node (ref "C9") (pin "1") (pinfunction "1_1") (pintype "passive"))
      (node (ref "R17") (pin "2") (pinfunction "2_2") (pintype "passive"))
      (node (ref "X4") (pin "P$1") (pinfunction "1_P$1") (pintype "passive"))
    )
    (net (code "68") (name "unconnected-(ADCL-Pad3)") (class "Default")
      (node (ref "ADCL") (pin "3") (pinfunction "3_3") (pintype "passive"))
    )
    (net (code "69") (name "unconnected-(ADCL-Pad4)") (class "Default")
      (node (ref "ADCL") (pin "4") (pinfunction "4_4") (pintype "passive"))
    )
    (net (code "70") (name "unconnected-(ADCL-Pad7)") (class "Default")
      (node (ref "ADCL") (pin "7") (pinfunction "7_7") (pintype "passive"))
    )
    (net (code "71") (name "unconnected-(ADCL-Pad8)") (class "Default")
      (node (ref "ADCL") (pin "8") (pinfunction "8_8") (pintype "passive"))
    )
    (net (code "72") (name "unconnected-(CANBUS-Pad4)") (class "Default")
      (node (ref "CANBUS") (pin "4") (pinfunction "4_4") (pintype "passive"))
    )
    (net (code "73") (name "unconnected-(CANBUS-Pad5)") (class "Default")
      (node (ref "CANBUS") (pin "5") (pinfunction "5_5") (pintype "passive"))
    )
    (net (code "74") (name "unconnected-(CANBUS-Pad9)") (class "Default")
      (node (ref "CANBUS") (pin "9") (pinfunction "9_9") (pintype "passive"))
    )
    (net (code "75") (name "unconnected-(DIGITAL_0-7-Pad4)") (class "Default")
      (node (ref "DIGITAL_0-7") (pin "4") (pinfunction "4_4") (pintype "passive"))
    )
    (net (code "76") (name "unconnected-(DIGITAL_0-7-Pad5)") (class "Default")
      (node (ref "DIGITAL_0-7") (pin "5") (pinfunction "5_5") (pintype "passive"))
    )
    (net (code "77") (name "unconnected-(DIGITAL_0-7-Pad8)") (class "Default")
      (node (ref "DIGITAL_0-7") (pin "8") (pinfunction "8_8") (pintype "passive"))
    )
    (net (code "78") (name "unconnected-(DIGITAL_8-13-Pad1)") (class "Default")
      (node (ref "DIGITAL_8-13") (pin "1") (pinfunction "1_1") (pintype "passive"))
    )
    (net (code "79") (name "unconnected-(DIGITAL_8-13-Pad2)") (class "Default")
      (node (ref "DIGITAL_8-13") (pin "2") (pinfunction "2_2") (pintype "passive"))
    )
    (net (code "80") (name "unconnected-(DIGITAL_8-13-Pad3)") (class "Default")
      (node (ref "DIGITAL_8-13") (pin "3") (pinfunction "3_3") (pintype "passive"))
    )
    (net (code "81") (name "unconnected-(DIGITAL_8-13-Pad4)") (class "Default")
      (node (ref "DIGITAL_8-13") (pin "4") (pinfunction "4_4") (pintype "passive"))
    )
    (net (code "82") (name "unconnected-(DIGITAL_8-13-Pad5)") (class "Default")
      (node (ref "DIGITAL_8-13") (pin "5") (pinfunction "5_5") (pintype "passive"))
    )
    (net (code "83") (name "unconnected-(DIGITAL_8-13-Pad6)") (class "Default")
      (node (ref "DIGITAL_8-13") (pin "6") (pinfunction "6_6") (pintype "passive"))
    )
    (net (code "84") (name "unconnected-(DIGITAL_8-13-Pad8)") (class "Default")
      (node (ref "DIGITAL_8-13") (pin "8") (pinfunction "8_8") (pintype "passive"))
    )
    (net (code "85") (name "unconnected-(DIGITAL_14-21-Pad1)") (class "Default")
      (node (ref "DIGITAL_14-21") (pin "1") (pinfunction "1_1") (pintype "passive"))
    )
    (net (code "86") (name "unconnected-(DIGITAL_14-21-Pad2)") (class "Default")
      (node (ref "DIGITAL_14-21") (pin "2") (pinfunction "2_2") (pintype "passive"))
    )
    (net (code "87") (name "unconnected-(DIGITAL_14-21-Pad3)") (class "Default")
      (node (ref "DIGITAL_14-21") (pin "3") (pinfunction "3_3") (pintype "passive"))
    )
    (net (code "88") (name "unconnected-(DIGITAL_14-21-Pad4)") (class "Default")
      (node (ref "DIGITAL_14-21") (pin "4") (pinfunction "4_4") (pintype "passive"))
    )
    (net (code "89") (name "unconnected-(DIGITAL_14-21-Pad5)") (class "Default")
      (node (ref "DIGITAL_14-21") (pin "5") (pinfunction "5_5") (pintype "passive"))
    )
    (net (code "90") (name "unconnected-(DIGITAL_14-21-Pad6)") (class "Default")
      (node (ref "DIGITAL_14-21") (pin "6") (pinfunction "6_6") (pintype "passive"))
    )
    (net (code "91") (name "unconnected-(IC1_2515A-CLKOUT-Pad3)") (class "Default")
      (node (ref "IC1_2515") (pin "3") (pinfunction "CLKOUT_3") (pintype "output"))
    )
    (net (code "92") (name "unconnected-(IC1_2515A-RX0BF-Pad11)") (class "Default")
      (node (ref "IC1_2515") (pin "11") (pinfunction "RX0BF_11") (pintype "output"))
    )
    (net (code "93") (name "unconnected-(IC1_2515A-RX1BF-Pad10)") (class "Default")
      (node (ref "IC1_2515") (pin "10") (pinfunction "RX1BF_10") (pintype "output"))
    )
    (net (code "94") (name "unconnected-(IC2_2551-VREF-Pad8)") (class "Default")
      (node (ref "IC2_2551") (pin "8") (pinfunction "VREF_8") (pintype "bidirectional"))
    )
    (net (code "95") (name "unconnected-(MEGA_EXPANSION-Pad9)") (class "Default")
      (node (ref "MEGA_EXPANSION") (pin "9") (pinfunction "9_9") (pintype "passive"))
    )
    (net (code "96") (name "unconnected-(MEGA_EXPANSION-Pad10)") (class "Default")
      (node (ref "MEGA_EXPANSION") (pin "10") (pinfunction "10_10") (pintype "passive"))
    )
    (net (code "97") (name "unconnected-(MEGA_EXPANSION-Pad11)") (class "Default")
      (node (ref "MEGA_EXPANSION") (pin "11") (pinfunction "11_11") (pintype "passive"))
    )
    (net (code "98") (name "unconnected-(MEGA_EXPANSION-Pad12)") (class "Default")
      (node (ref "MEGA_EXPANSION") (pin "12") (pinfunction "12_12") (pintype "passive"))
    )
    (net (code "99") (name "unconnected-(MEGA_EXPANSION-Pad13)") (class "Default")
      (node (ref "MEGA_EXPANSION") (pin "13") (pinfunction "13_13") (pintype "passive"))
    )
    (net (code "100") (name "unconnected-(MEGA_EXPANSION-Pad14)") (class "Default")
      (node (ref "MEGA_EXPANSION") (pin "14") (pinfunction "14_14") (pintype "passive"))
    )
    (net (code "101") (name "unconnected-(MEGA_EXPANSION-Pad15)") (class "Default")
      (node (ref "MEGA_EXPANSION") (pin "15") (pinfunction "15_15") (pintype "passive"))
    )
    (net (code "102") (name "unconnected-(MEGA_EXPANSION-Pad16)") (class "Default")
      (node (ref "MEGA_EXPANSION") (pin "16") (pinfunction "16_16") (pintype "passive"))
    )
    (net (code "103") (name "unconnected-(MEGA_EXPANSION-Pad21)") (class "Default")
      (node (ref "MEGA_EXPANSION") (pin "21") (pinfunction "21_21") (pintype "passive"))
    )
    (net (code "104") (name "unconnected-(MEGA_EXPANSION-Pad23)") (class "Default")
      (node (ref "MEGA_EXPANSION") (pin "23") (pinfunction "23_23") (pintype "passive"))
    )
    (net (code "105") (name "unconnected-(MEGA_EXPANSION-Pad24)") (class "Default")
      (node (ref "MEGA_EXPANSION") (pin "24") (pinfunction "24_24") (pintype "passive"))
    )
    (net (code "106") (name "unconnected-(MEGA_EXPANSION-Pad25)") (class "Default")
      (node (ref "MEGA_EXPANSION") (pin "25") (pinfunction "25_25") (pintype "passive"))
    )
    (net (code "107") (name "unconnected-(MEGA_EXPANSION-Pad26)") (class "Default")
      (node (ref "MEGA_EXPANSION") (pin "26") (pinfunction "26_26") (pintype "passive"))
    )
    (net (code "108") (name "unconnected-(MEGA_EXPANSION-Pad27)") (class "Default")
      (node (ref "MEGA_EXPANSION") (pin "27") (pinfunction "27_27") (pintype "passive"))
    )
    (net (code "109") (name "unconnected-(MEGA_EXPANSION-Pad28)") (class "Default")
      (node (ref "MEGA_EXPANSION") (pin "28") (pinfunction "28_28") (pintype "passive"))
    )
    (net (code "110") (name "unconnected-(MEGA_EXPANSION-Pad29)") (class "Default")
      (node (ref "MEGA_EXPANSION") (pin "29") (pinfunction "29_29") (pintype "passive"))
    )
    (net (code "111") (name "unconnected-(MEGA_EXPANSION-Pad30)") (class "Default")
      (node (ref "MEGA_EXPANSION") (pin "30") (pinfunction "30_30") (pintype "passive"))
    )
    (net (code "112") (name "unconnected-(MEGA_EXPANSION-Pad31)") (class "Default")
      (node (ref "MEGA_EXPANSION") (pin "31") (pinfunction "31_31") (pintype "passive"))
    )
    (net (code "113") (name "unconnected-(MEGA_EXPANSION-Pad33)") (class "Default")
      (node (ref "MEGA_EXPANSION") (pin "33") (pinfunction "33_33") (pintype "passive"))
    )
  )
)
